# regulateur_de_tension.net
KiCad netlist of a schematic drawn in Altium Designer
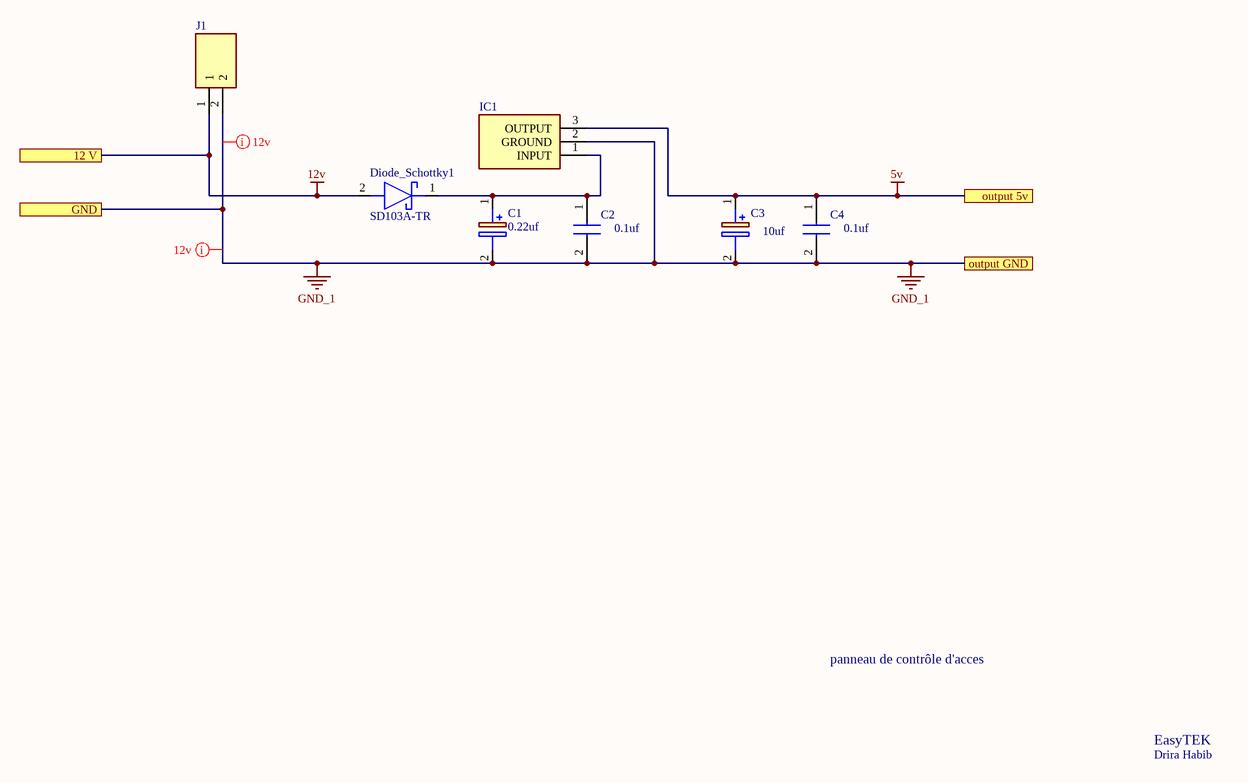
[diagram p0: regulateur de tension.SchDoc]

(export (version "E")
  (design (tool "Eeschema 10.0.6"))
  (components
    (comp (ref "C1")
      (value "0.22uf")
      (footprint "SamacSys:CAPPRD200W52D500H1250")
      (description "Capacitor Polarised")
      (fields
        (field (name "MANUFACTURER_PART_NUMBER") "860010772002")
        (field (name "MOUSER PART NUMBER") "710-860010772002")
      )
      (libsource (lib "SamacSys") (part "860010772002"))
    )
    (comp (ref "C2")
      (value "0.1uf")
      (footprint "SamacSys:RDE5C1H330J0M1H03A")
      (description "Capacitor")
      (fields
        (field (name "MANUFACTURER_PART_NUMBER") "RDER71E104K0K1H03B")
        (field (name "MOUSER PART NUMBER") "81-RDER71E104K0K1H3B")
      )
      (libsource (lib "*") (part "RDER71E104K0K1H03B"))
    )
    (comp (ref "C3")
      (value "10uf")
      (footprint "SamacSys:CAPPRD200W55D500H1250")
      (description "Capacitor Polarised")
      (fields (field (name "MANUFACTURER_PART_NUMBER") "EEUFR1H100"))
      (libsource (lib "*") (part "EEUFR1H100"))
    )
    (comp (ref "C4")
      (value "0.1uf")
      (footprint "SamacSys:RDE5C1H330J0M1H03A")
      (description "Capacitor")
      (fields
        (field (name "MANUFACTURER_PART_NUMBER") "RDER71E104K0K1H03B")
        (field (name "MOUSER PART NUMBER") "81-RDER71E104K0K1H3B")
      )
      (libsource (lib "*") (part "RDER71E104K0K1H03B"))
    )
    (comp (ref "Diode_Schottky1")
      (value "SD103A-TR")
      (footprint "SamacSys:DIOAD950W60L350D150")
      (description "Schottky Diode")
      (fields (field (name "MOUSER PART NUMBER") "625-SD103A"))
      (libsource (lib "*") (part "SD103A-TR"))
    )
    (comp (ref "IC1")
      (value "L7805CV")
      (footprint "SamacSys:TO255P460X1020X2008-3P")
      (description "Integrated Circuit")
      (fields (field (name "MOUSER PART NUMBER") "511-L7805CV"))
      (libsource (lib "*") (part "L7805CV"))
    )
    (comp (ref "J1")
      (value "1546215-2")
      (footprint "SamacSys:15462152")
      (description "Connector")
      (fields (field (name "MOUSER PART NUMBER") "571-1546215-2"))
      (libsource (lib "*") (part "1546215-2"))
    )
  )
  (nets
    (net (code "1") (name "5v") (class "Default")
      (node (ref "C3") (pin "1") (pinfunction "+_1") (pintype "passive"))
      (node (ref "C4") (pin "1") (pinfunction "1_1") (pintype "passive"))
      (node (ref "IC1") (pin "3") (pinfunction "OUTPUT_3") (pintype "passive"))
    )
    (net (code "2") (name "12v") (class "Default")
      (node (ref "Diode_Schottky1") (pin "2") (pinfunction "A_2") (pintype "passive"))
      (node (ref "J1") (pin "1") (pinfunction "1_1") (pintype "passive"))
    )
    (net (code "3") (name "GND_1") (class "Default")
      (node (ref "C1") (pin "2") (pinfunction "-_2") (pintype "passive"))
      (node (ref "C2") (pin "2") (pinfunction "2_2") (pintype "passive"))
      (node (ref "C3") (pin "2") (pinfunction "-_2") (pintype "passive"))
      (node (ref "C4") (pin "2") (pinfunction "2_2") (pintype "passive"))
      (node (ref "IC1") (pin "2") (pinfunction "GROUND_2") (pintype "passive"))
      (node (ref "J1") (pin "2") (pinfunction "2_2") (pintype "passive"))
    )
    (net (code "4") (name "Net-(C1-+)") (class "Default")
      (node (ref "C1") (pin "1") (pinfunction "+_1") (pintype "passive"))
      (node (ref "C2") (pin "1") (pinfunction "1_1") (pintype "passive"))
      (node (ref "Diode_Schottky1") (pin "1") (pinfunction "K_1") (pintype "passive"))
      (node (ref "IC1") (pin "1") (pinfunction "INPUT_1") (pintype "passive"))
    )
  )
)
